# X09-V2_0_0.net
KiCad netlist of a schematic drawn in Altium Designer
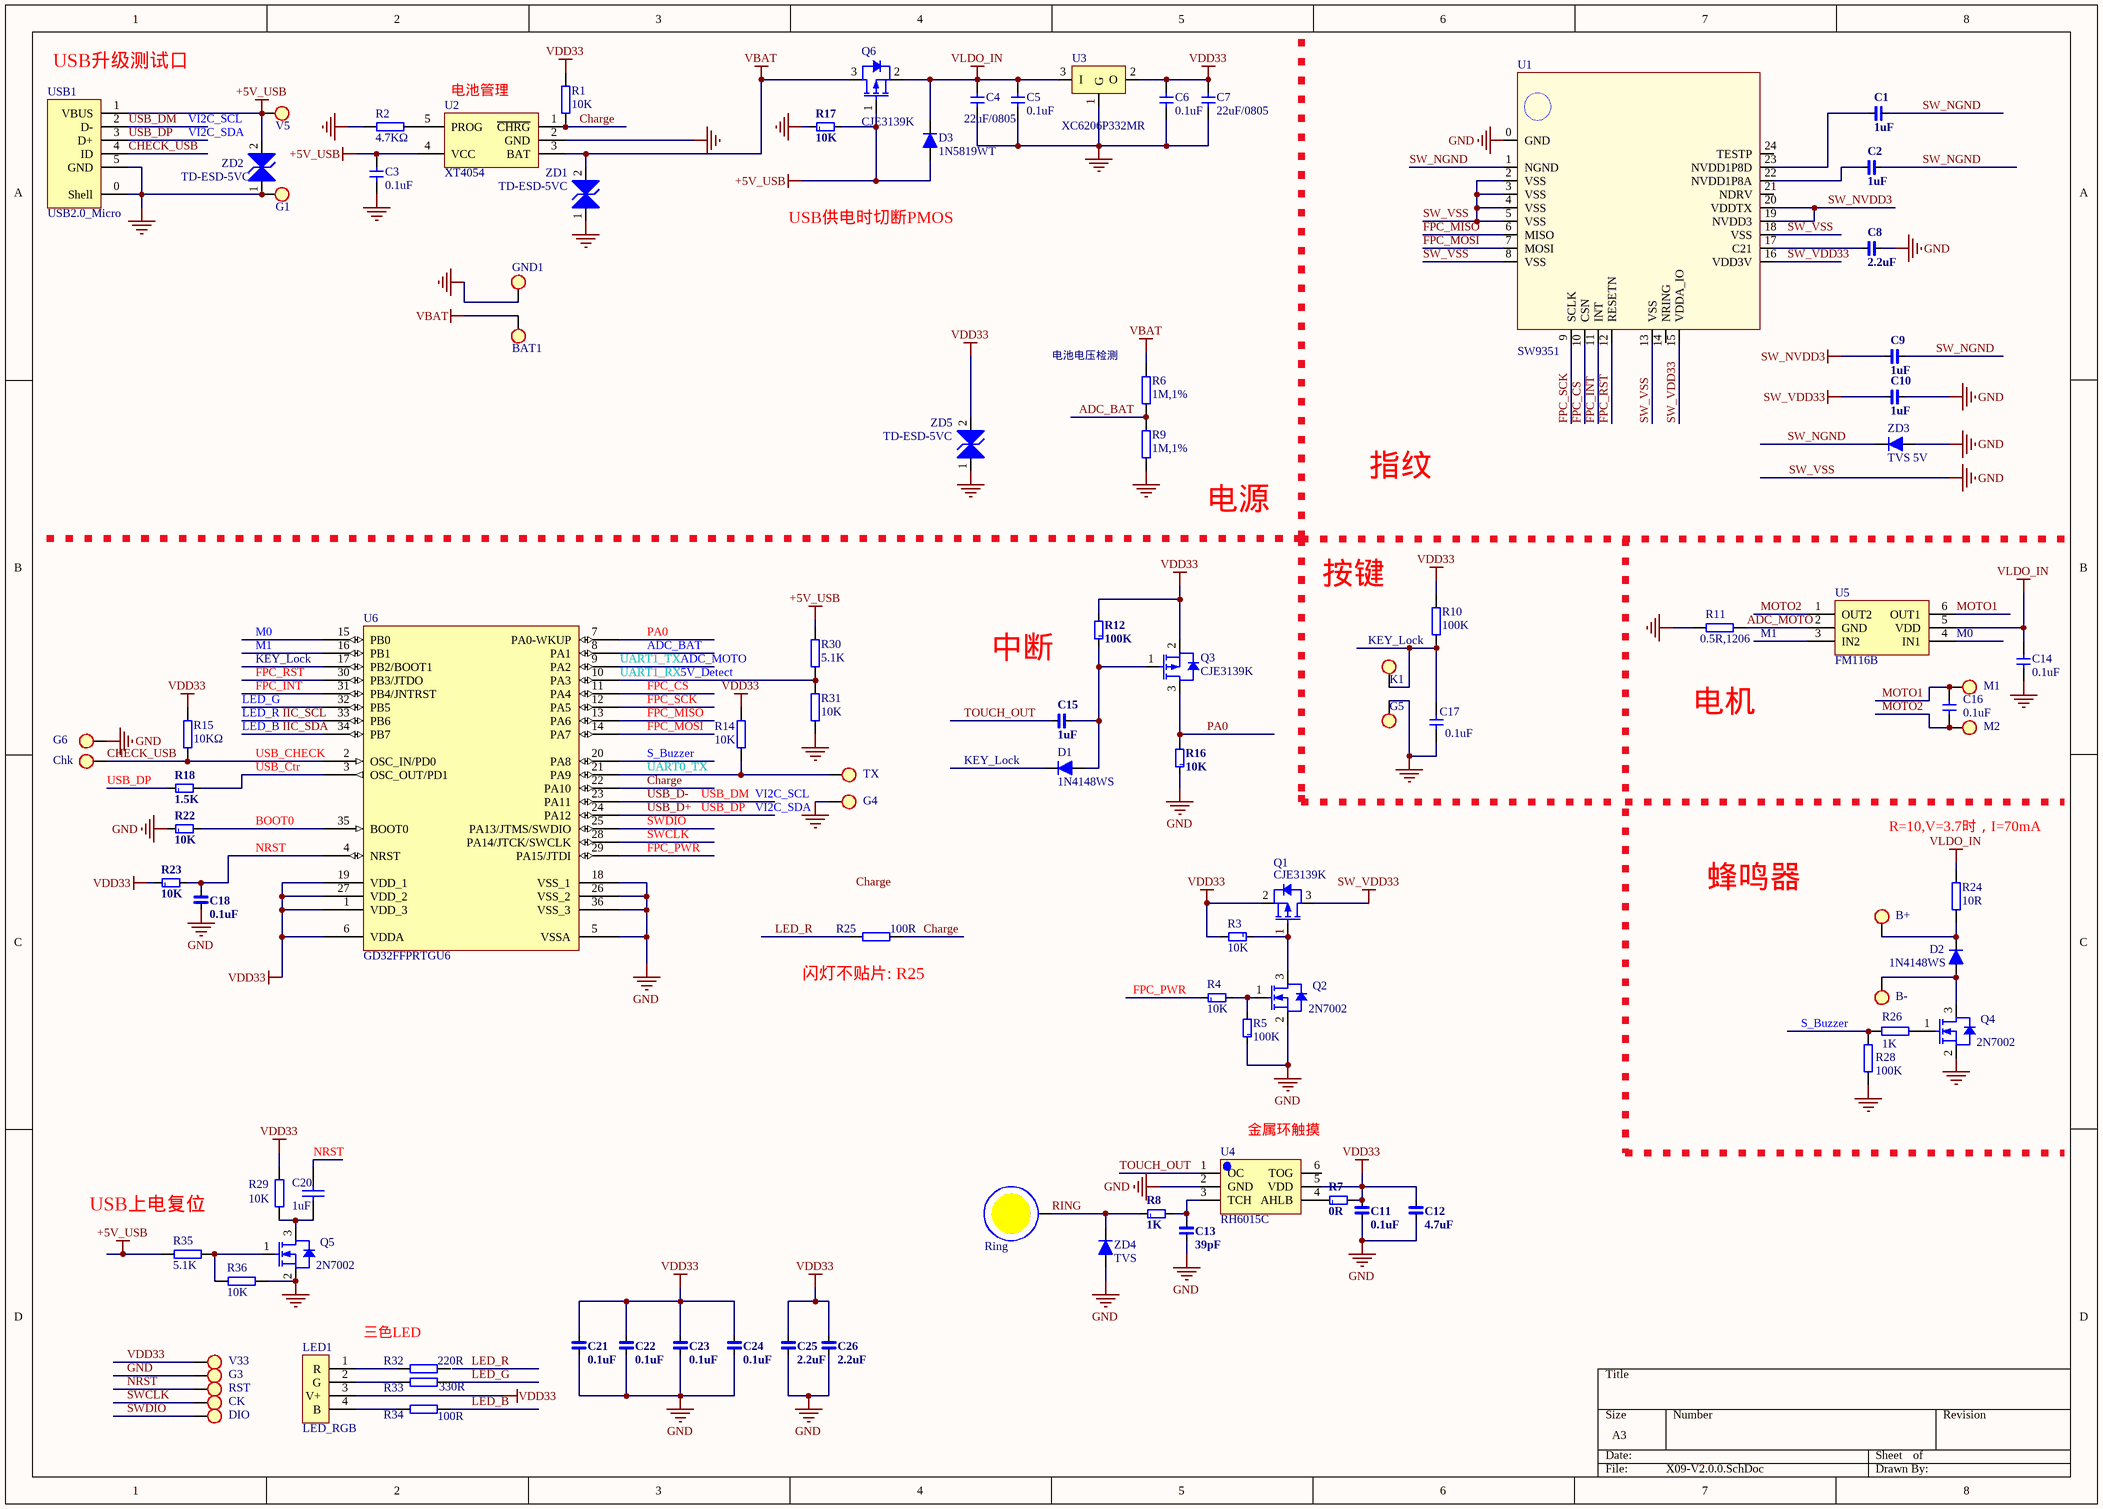
[diagram p0: X09-V2.0.0.SchDoc]

(export (version "E")
  (design (tool "Eeschema 10.0.6"))
  (components
    (comp (ref "B+") (value "TestPoint") (footprint "TEST Point") (libsource (lib "") (part "TestPoint_1")))
    (comp (ref "B-") (value "TestPoint") (footprint "TEST Point") (libsource (lib "") (part "TestPoint_1")))
    (comp (ref "BAT1") (value "TestPoint") (footprint "TEST Point") (libsource (lib "") (part "TestPoint_1")))
    (comp (ref "C1")
      (value "1uF")
      (footprint "0402C")
      (description "Capacitor")
      (libsource (lib "S3C2416") (part "CAP_0402A"))
    )
    (comp (ref "C2")
      (value "1uF")
      (footprint "0402C")
      (description "Capacitor")
      (libsource (lib "S3C2416") (part "CAP_0402A"))
    )
    (comp (ref "C3")
      (value "0.1uF")
      (footprint "0402C")
      (description "Capacitor")
      (libsource (lib "*") (part "CAP"))
    )
    (comp (ref "C4")
      (value "22uF/0805")
      (footprint "0603c")
      (description "Capacitor")
      (libsource (lib "*") (part "CAP"))
    )
    (comp (ref "C5")
      (value "0.1uF")
      (footprint "0402C")
      (description "Capacitor")
      (libsource (lib "*") (part "CAP"))
    )
    (comp (ref "C6")
      (value "0.1uF")
      (footprint "0402C")
      (description "Capacitor")
      (libsource (lib "*") (part "CAP"))
    )
    (comp (ref "C7")
      (value "22uF/0805")
      (footprint "0603c")
      (description "Capacitor")
      (libsource (lib "*") (part "CAP"))
    )
    (comp (ref "C8")
      (value "2.2uF")
      (footprint "0402C")
      (description "Capacitor")
      (libsource (lib "S3C2416") (part "CAP_0402A"))
    )
    (comp (ref "C9")
      (value "1uF")
      (footprint "0402C")
      (description "Capacitor")
      (libsource (lib "S3C2416") (part "CAP_0402A"))
    )
    (comp (ref "C10")
      (value "1uF")
      (footprint "0402C")
      (description "Capacitor")
      (libsource (lib "S3C2416") (part "CAP_0402A"))
    )
    (comp (ref "C11")
      (value "0.1uF")
      (footprint "0402C")
      (description "Capacitor")
      (libsource (lib "S3C2416") (part "CAP_0402A"))
    )
    (comp (ref "C12")
      (value "4.7uF")
      (footprint "0402C")
      (description "Capacitor")
      (libsource (lib "S3C2416") (part "CAP_0402A"))
    )
    (comp (ref "C13")
      (value "39pF")
      (footprint "0402C")
      (description "Capacitor")
      (libsource (lib "S3C2416") (part "CAP_0402A"))
    )
    (comp (ref "C14")
      (value "0.1uF")
      (footprint "0402C")
      (description "Capacitor")
      (libsource (lib "*") (part "CAP"))
    )
    (comp (ref "C15")
      (value "1uF")
      (footprint "0402C")
      (description "Capacitor")
      (libsource (lib "S3C2416") (part "CAP_0402A"))
    )
    (comp (ref "C16")
      (value "0.1uF")
      (footprint "0402C")
      (description "Capacitor")
      (libsource (lib "*") (part "CAP"))
    )
    (comp (ref "C17")
      (value "0.1uF")
      (footprint "0402C")
      (description "Capacitor")
      (libsource (lib "*") (part "CAP"))
    )
    (comp (ref "C18")
      (value "0.1uF")
      (footprint "0402C")
      (description "Capacitor")
      (libsource (lib "S3C2416") (part "CAP_0402A"))
    )
    (comp (ref "C20")
      (value "1uF")
      (footprint "0402C")
      (description "表贴电容")
      (libsource (lib "*") (part "50V/0.1uF"))
    )
    (comp (ref "C21")
      (value "0.1uF")
      (footprint "0402C")
      (description "Capacitor")
      (libsource (lib "S3C2416") (part "CAP_0402A"))
    )
    (comp (ref "C22")
      (value "0.1uF")
      (footprint "0402C")
      (description "Capacitor")
      (libsource (lib "S3C2416") (part "CAP_0402A"))
    )
    (comp (ref "C23")
      (value "0.1uF")
      (footprint "0402C")
      (description "Capacitor")
      (libsource (lib "S3C2416") (part "CAP_0402A"))
    )
    (comp (ref "C24")
      (value "0.1uF")
      (footprint "0402C")
      (description "Capacitor")
      (libsource (lib "S3C2416") (part "CAP_0402A"))
    )
    (comp (ref "C25")
      (value "2.2uF")
      (footprint "0402C")
      (description "Capacitor")
      (libsource (lib "S3C2416") (part "CAP_0402A"))
    )
    (comp (ref "C26")
      (value "2.2uF")
      (footprint "0402C")
      (description "Capacitor")
      (libsource (lib "S3C2416") (part "CAP_0402A"))
    )
    (comp (ref "Chk")
      (value "TestPoint")
      (footprint "TEST Point")
      (libsource (lib "SCH_LIB_WLF") (part "TestPoint"))
    )
    (comp (ref "CK")
      (value "TestPoint")
      (footprint "TEST Point")
      (libsource (lib "SCH_LIB_WLF") (part "TestPoint"))
    )
    (comp (ref "D1") (value "1N4148WS") (footprint "SOD-523") (libsource (lib "PadLock_V3.0") (part "DIODE")))
    (comp (ref "D2") (value "1N4148WS") (footprint "SOD-523") (libsource (lib "PadLock_V3.0") (part "DIODE")))
    (comp (ref "D3") (value "1N5819WT") (footprint "SOD-523") (libsource (lib "PadLock_V3.0") (part "DIODE")))
    (comp (ref "DIO")
      (value "TestPoint")
      (footprint "TEST Point")
      (libsource (lib "SCH_LIB_WLF") (part "TestPoint"))
    )
    (comp (ref "G1")
      (value "TestPoint")
      (footprint "TEST Point")
      (libsource (lib "SCH_LIB_WLF") (part "TestPoint"))
    )
    (comp (ref "G3")
      (value "TestPoint")
      (footprint "TEST Point")
      (libsource (lib "SCH_LIB_WLF") (part "TestPoint"))
    )
    (comp (ref "G4")
      (value "TestPoint")
      (footprint "TEST Point")
      (libsource (lib "SCH_LIB_WLF") (part "TestPoint"))
    )
    (comp (ref "G5") (value "TestPoint") (footprint "TEST Point") (libsource (lib "") (part "TestPoint_1")))
    (comp (ref "G6")
      (value "TestPoint")
      (footprint "TEST Point")
      (libsource (lib "SCH_LIB_WLF") (part "TestPoint"))
    )
    (comp (ref "GND1") (value "TestPoint") (footprint "TEST Point") (libsource (lib "") (part "TestPoint_1")))
    (comp (ref "K1") (value "TestPoint") (footprint "TEST Point") (libsource (lib "") (part "TestPoint_1")))
    (comp (ref "LED1")
      (value "LED_RGB")
      (footprint "LED0603_RGB")
      (libsource (lib "SCH_LIB_WLF") (part "LED_RGB"))
    )
    (comp (ref "M1")
      (value "TestPoint")
      (footprint "TEST Point")
      (libsource (lib "SCH_LIB_WLF") (part "TestPoint"))
    )
    (comp (ref "M2")
      (value "TestPoint")
      (footprint "TEST Point")
      (libsource (lib "SCH_LIB_WLF") (part "TestPoint"))
    )
    (comp (ref "Q1")
      (value "CJE3139K")
      (footprint "SOT-523")
      (description "P-Channel MOSFET")
      (fields (field (name "PUBLISHER") "Altium Limited"))
      (libsource (lib "SCH_LIB_WLF") (part "MOSFET-P"))
    )
    (comp (ref "Q2")
      (value "2N7002")
      (footprint "SOT-523")
      (description "N-Channel MOSFET")
      (fields (field (name "PUBLISHER") "Altium Limited"))
      (libsource (lib "SCH_LIB_WLF") (part "MOSFET-N"))
    )
    (comp (ref "Q3")
      (value "CJE3139K")
      (footprint "SOT-523")
      (description "P-Channel MOSFET")
      (fields (field (name "PUBLISHER") "Altium Limited"))
      (libsource (lib "") (part "MOSFET-P_1"))
    )
    (comp (ref "Q4")
      (value "2N7002")
      (footprint "SOT-523")
      (description "N-Channel MOSFET")
      (fields (field (name "PUBLISHER") "Altium Limited"))
      (libsource (lib "SCH_LIB_WLF") (part "MOSFET-N"))
    )
    (comp (ref "Q5")
      (value "2N7002")
      (footprint "SOT-523")
      (description "N-Channel MOSFET")
      (fields (field (name "PUBLISHER") "Altium Limited"))
      (libsource (lib "SCH_LIB_WLF") (part "MOSFET-N"))
    )
    (comp (ref "Q6")
      (value "CJE3139K")
      (footprint "SOT-523")
      (description "P-Channel MOSFET")
      (fields (field (name "PUBLISHER") "Altium Limited"))
      (libsource (lib "SCH_LIB_WLF") (part "MOSFET-P"))
    )
    (comp (ref "R1")
      (value "10K")
      (footprint "0402R")
      (description "直插/表贴电阻")
      (libsource (lib "*") (part "10KΩ"))
    )
    (comp (ref "R2")
      (value "4.7KΩ")
      (footprint "0402R")
      (description "直插/表贴电阻")
      (libsource (lib "*") (part "10KΩ"))
    )
    (comp (ref "R3")
      (value "10K")
      (footprint "0402R")
      (description "Resistor")
      (libsource (lib "S3C2416") (part "RES_0603A"))
    )
    (comp (ref "R4")
      (value "10K")
      (footprint "0402R")
      (description "Resistor")
      (libsource (lib "S3C2416") (part "RES_0603A"))
    )
    (comp (ref "R5")
      (value "100K")
      (footprint "0402R")
      (description "Resistor")
      (libsource (lib "S3C2416") (part "RES_0603A"))
    )
    (comp (ref "R6")
      (value "1M,1%")
      (footprint "0402R")
      (description "直插/表贴电阻")
      (libsource (lib "*") (part "10KΩ"))
    )
    (comp (ref "R7")
      (value "0R")
      (footprint "0402R")
      (description "Resistor")
      (libsource (lib "S3C2416") (part "RES_0402A"))
    )
    (comp (ref "R8")
      (value "1K")
      (footprint "0402R")
      (description "Resistor")
      (libsource (lib "S3C2416") (part "RES_0402A"))
    )
    (comp (ref "R9")
      (value "1M,1%")
      (footprint "0402R")
      (description "直插/表贴电阻")
      (libsource (lib "*") (part "10KΩ"))
    )
    (comp (ref "R10")
      (value "100K")
      (footprint "0402R")
      (description "直插/表贴电阻")
      (libsource (lib "*") (part "10KΩ"))
    )
    (comp (ref "R11")
      (value "0.5R,1206")
      (footprint "1206")
      (description "直插/表贴电阻")
      (libsource (lib "*") (part "10KΩ"))
    )
    (comp (ref "R12")
      (value "100K")
      (footprint "0402R")
      (description "Resistor")
      (libsource (lib "S3C2416") (part "RES_0402A"))
    )
    (comp (ref "R14")
      (value "10K")
      (footprint "0402R")
      (description "直插/表贴电阻")
      (libsource (lib "*") (part "10KΩ"))
    )
    (comp (ref "R15")
      (value "10KΩ")
      (footprint "0402R")
      (description "直插/表贴电阻")
      (libsource (lib "*") (part "10KΩ"))
    )
    (comp (ref "R16")
      (value "10K")
      (footprint "0402R")
      (description "Resistor")
      (libsource (lib "S3C2416") (part "RES_0402A"))
    )
    (comp (ref "R17")
      (value "10K")
      (footprint "0402R")
      (description "Resistor")
      (libsource (lib "S3C2416") (part "RES_0402A"))
    )
    (comp (ref "R18")
      (value "1.5K")
      (footprint "0402R")
      (description "Resistor")
      (libsource (lib "S3C2416") (part "RES_0402A"))
    )
    (comp (ref "R22")
      (value "10K")
      (footprint "0402R")
      (description "Resistor")
      (libsource (lib "S3C2416") (part "RES_0402A"))
    )
    (comp (ref "R23")
      (value "10K")
      (footprint "0402R")
      (description "Resistor")
      (libsource (lib "S3C2416") (part "RES_0402A"))
    )
    (comp (ref "R24") (value "10R") (footprint "0402R") (libsource (lib "*") (part "RES2")))
    (comp (ref "R25")
      (value "100R")
      (footprint "0402R")
      (description "直插/表贴电阻")
      (libsource (lib "*") (part "10KΩ"))
    )
    (comp (ref "R26")
      (value "1K")
      (footprint "0402R")
      (description "直插/表贴电阻")
      (libsource (lib "*") (part "10KΩ"))
    )
    (comp (ref "R28")
      (value "100K")
      (footprint "0402R")
      (description "直插/表贴电阻")
      (libsource (lib "*") (part "10KΩ"))
    )
    (comp (ref "R29")
      (value "10K")
      (footprint "0402R")
      (description "直插/表贴电阻")
      (libsource (lib "*") (part "10KΩ"))
    )
    (comp (ref "R30")
      (value "5.1K")
      (footprint "0402R")
      (description "直插/表贴电阻")
      (libsource (lib "*") (part "10KΩ"))
    )
    (comp (ref "R31")
      (value "10K")
      (footprint "0402R")
      (description "直插/表贴电阻")
      (libsource (lib "*") (part "10KΩ"))
    )
    (comp (ref "R32")
      (value "220R")
      (footprint "0402R")
      (description "直插/表贴电阻")
      (libsource (lib "*") (part "10KΩ"))
    )
    (comp (ref "R33")
      (value "330R")
      (footprint "0402R")
      (description "直插/表贴电阻")
      (libsource (lib "*") (part "10KΩ"))
    )
    (comp (ref "R34")
      (value "100R")
      (footprint "0402R")
      (description "直插/表贴电阻")
      (libsource (lib "*") (part "10KΩ"))
    )
    (comp (ref "R35")
      (value "5.1K")
      (footprint "0402R")
      (description "直插/表贴电阻")
      (libsource (lib "*") (part "10KΩ"))
    )
    (comp (ref "R36")
      (value "10K")
      (footprint "0402R")
      (description "直插/表贴电阻")
      (libsource (lib "*") (part "10KΩ"))
    )
    (comp (ref "Ring")
      (value "TouchKey")
      (footprint "TouchPad")
      (libsource (lib "SCH_LIB_WLF") (part "TouchKey"))
    )
    (comp (ref "RST")
      (value "TestPoint")
      (footprint "TEST Point")
      (libsource (lib "SCH_LIB_WLF") (part "TestPoint"))
    )
    (comp (ref "TX")
      (value "TestPoint")
      (footprint "TEST Point")
      (libsource (lib "SCH_LIB_WLF") (part "TestPoint"))
    )
    (comp (ref "U1") (value "SW9351") (footprint "SW9551L_1") (libsource (lib "Sheet2") (part "SW9551_120")))
    (comp (ref "U2")
      (value "XT4054")
      (footprint "LC-SOT-23-5")
      (description "电池管理芯片")
      (libsource (lib "SCH_LIB_WLF") (part "4054"))
    )
    (comp (ref "U3")
      (value "XC6206P332MR-G")
      (footprint "SOT-23-standard")
      (description "电源IC")
      (fields (field (name "1ERP_VALUE") "XC6206P332MR"))
      (libsource (lib "SCH") (part "XC6206P182MR-G"))
    )
    (comp (ref "U4")
      (value "RH6015C")
      (footprint "LC-SOT-23-6")
      (description "单通道触摸IC,SOT23-6")
      (libsource (lib "SCH_LIB_WLF") (part "RH6015C"))
    )
    (comp (ref "U5")
      (value "FM116B")
      (footprint "LC-SOT-23-6")
      (description "电机驱动")
      (libsource (lib "SCH_LIB_WLF") (part "FM116B"))
    )
    (comp (ref "U6")
      (value "GD32FFPRTGU6")
      (footprint "GD32GU6-TOP")
      (libsource (lib "*") (part "GD32FFPRTGU6"))
    )
    (comp (ref "USB1")
      (value "USB2.0_Micro")
      (footprint "USB2.0_Micro")
      (libsource (lib "SCH_LIB_WLF") (part "USB2.0_Mini_Micro"))
    )
    (comp (ref "V5")
      (value "TestPoint")
      (footprint "TEST Point")
      (libsource (lib "SCH_LIB_WLF") (part "TestPoint"))
    )
    (comp (ref "V33")
      (value "TestPoint")
      (footprint "TEST Point")
      (libsource (lib "SCH_LIB_WLF") (part "TestPoint"))
    )
    (comp (ref "ZD1")
      (value "TD-ESD-5VC")
      (footprint "SOD-523")
      (libsource (lib "MULTI_TOOL_V 1.6") (part "TVS-DUAL"))
    )
    (comp (ref "ZD2")
      (value "TD-ESD-5VC")
      (footprint "SOD-523")
      (libsource (lib "MULTI_TOOL_V 1.6") (part "TVS-DUAL"))
    )
    (comp (ref "ZD3") (value "TVS 5V") (footprint "SOD-523") (libsource (lib "PadLock_V3.0") (part "DIODE")))
    (comp (ref "ZD4") (value "TVS") (footprint "SOD-523") (libsource (lib "PadLock_V3.0") (part "DIODE")))
    (comp (ref "ZD5")
      (value "TD-ESD-5VC")
      (footprint "SOD-523")
      (libsource (lib "MULTI_TOOL_V 1.6") (part "TVS-DUAL"))
    )
  )
  (nets
    (net (code "1") (name "+5V_USB") (class "Default")
      (node (ref "C3") (pin "1") (pinfunction "1_1") (pintype "passive"))
      (node (ref "D3") (pin "1") (pinfunction "A_1") (pintype "passive"))
      (node (ref "Q6") (pin "1") (pinfunction "G_1") (pintype "passive"))
      (node (ref "R17") (pin "2") (pinfunction "2_2") (pintype "passive"))
      (node (ref "R30") (pin "1") (pinfunction "1_1") (pintype "passive"))
      (node (ref "R35") (pin "2") (pinfunction "2_2") (pintype "passive"))
      (node (ref "U2") (pin "4") (pinfunction "VCC_4") (pintype "passive"))
      (node (ref "USB1") (pin "1") (pinfunction "VBUS_1") (pintype "passive"))
      (node (ref "V5") (pin "1") (pinfunction "Test_1") (pintype "passive"))
      (node (ref "ZD2") (pin "2") (pinfunction "A_2") (pintype "passive"))
    )
    (net (code "2") (name "/5V_Detect") (class "Default")
      (node (ref "R30") (pin "2") (pinfunction "2_2") (pintype "passive"))
      (node (ref "R31") (pin "1") (pinfunction "1_1") (pintype "passive"))
      (node (ref "U6") (pin "10") (pinfunction "PA3_10") (pintype "bidirectional"))
    )
    (net (code "3") (name "/ADC_BAT") (class "Default")
      (node (ref "R6") (pin "2") (pinfunction "2_2") (pintype "passive"))
      (node (ref "R9") (pin "1") (pinfunction "1_1") (pintype "passive"))
      (node (ref "U6") (pin "8") (pinfunction "PA1_8") (pintype "bidirectional"))
    )
    (net (code "4") (name "/ADC_MOTO") (class "Default")
      (node (ref "R11") (pin "2") (pinfunction "2_2") (pintype "passive"))
      (node (ref "U5") (pin "2") (pinfunction "GND_2") (pintype "passive"))
      (node (ref "U6") (pin "9") (pinfunction "PA2_9") (pintype "bidirectional"))
    )
    (net (code "5") (name "/BOOT0") (class "Default")
      (node (ref "R22") (pin "2") (pinfunction "2_2") (pintype "passive"))
      (node (ref "U6") (pin "35") (pinfunction "BOOT0_35") (pintype "input"))
    )
    (net (code "6") (name "/CHECK_USB") (class "Default")
      (node (ref "Chk") (pin "1") (pinfunction "Test_1") (pintype "passive"))
      (node (ref "R15") (pin "1") (pinfunction "1_1") (pintype "passive"))
      (node (ref "U6") (pin "2") (pinfunction "OSC_IN/PD0_2") (pintype "input"))
      (node (ref "USB1") (pin "4") (pinfunction "ID_4") (pintype "passive"))
    )
    (net (code "7") (name "/Charge") (class "Default")
      (node (ref "R1") (pin "2") (pinfunction "2_2") (pintype "passive"))
      (node (ref "R25") (pin "1") (pinfunction "1_1") (pintype "passive"))
      (node (ref "U2") (pin "1") (pinfunction "~{CHRG}_1") (pintype "passive"))
      (node (ref "U6") (pin "22") (pinfunction "PA10_22") (pintype "bidirectional"))
    )
    (net (code "8") (name "/FPC_CS") (class "Default")
      (node (ref "U1") (pin "10") (pinfunction "CSN_10") (pintype "passive"))
      (node (ref "U6") (pin "11") (pinfunction "PA4_11") (pintype "bidirectional"))
    )
    (net (code "9") (name "/FPC_INT") (class "Default")
      (node (ref "U1") (pin "11") (pinfunction "INT_11") (pintype "passive"))
      (node (ref "U6") (pin "31") (pinfunction "PB4/JNTRST_31") (pintype "bidirectional"))
    )
    (net (code "10") (name "/FPC_MISO") (class "Default")
      (node (ref "U1") (pin "6") (pinfunction "MISO_6") (pintype "passive"))
      (node (ref "U6") (pin "13") (pinfunction "PA6_13") (pintype "bidirectional"))
    )
    (net (code "11") (name "/FPC_MOSI") (class "Default")
      (node (ref "U1") (pin "7") (pinfunction "MOSI_7") (pintype "passive"))
      (node (ref "U6") (pin "14") (pinfunction "PA7_14") (pintype "bidirectional"))
    )
    (net (code "12") (name "/FPC_PWR") (class "Default")
      (node (ref "R4") (pin "1") (pinfunction "1_1") (pintype "passive"))
      (node (ref "U6") (pin "29") (pinfunction "PA15/JTDI_29") (pintype "bidirectional"))
    )
    (net (code "13") (name "/FPC_RST") (class "Default")
      (node (ref "U1") (pin "12") (pinfunction "RESETN_12") (pintype "passive"))
      (node (ref "U6") (pin "30") (pinfunction "PB3/JTDO_30") (pintype "bidirectional"))
    )
    (net (code "14") (name "/FPC_SCK") (class "Default")
      (node (ref "U1") (pin "9") (pinfunction "SCLK_9") (pintype "passive"))
      (node (ref "U6") (pin "12") (pinfunction "PA5_12") (pintype "bidirectional"))
    )
    (net (code "15") (name "/IIC_SCL") (class "Default")
      (node (ref "R25") (pin "2") (pinfunction "2_2") (pintype "passive"))
      (node (ref "U6") (pin "33") (pinfunction "PB6_33") (pintype "bidirectional"))
    )
    (net (code "16") (name "/IIC_SDA") (class "Default")
      (node (ref "R34") (pin "1") (pinfunction "1_1") (pintype "passive"))
      (node (ref "U6") (pin "34") (pinfunction "PB7_34") (pintype "bidirectional"))
    )
    (net (code "17") (name "/KEY_Lock") (class "Default")
      (node (ref "C17") (pin "1") (pinfunction "1_1") (pintype "passive"))
      (node (ref "D1") (pin "2") (pinfunction "K_2") (pintype "passive"))
      (node (ref "K1") (pin "1") (pinfunction "Test_1") (pintype "passive"))
      (node (ref "R10") (pin "2") (pinfunction "2_2") (pintype "passive"))
      (node (ref "U6") (pin "17") (pinfunction "PB2/BOOT1_17") (pintype "bidirectional"))
    )
    (net (code "18") (name "/LED_G") (class "Default")
      (node (ref "R33") (pin "1") (pinfunction "1_1") (pintype "passive"))
      (node (ref "U6") (pin "32") (pinfunction "PB5_32") (pintype "bidirectional"))
    )
    (net (code "19") (name "/M0") (class "Default")
      (node (ref "U5") (pin "4") (pinfunction "IN1_4") (pintype "passive"))
      (node (ref "U6") (pin "15") (pinfunction "PB0_15") (pintype "bidirectional"))
    )
    (net (code "20") (name "/M1") (class "Default")
      (node (ref "U5") (pin "3") (pinfunction "IN2_3") (pintype "passive"))
      (node (ref "U6") (pin "16") (pinfunction "PB1_16") (pintype "bidirectional"))
    )
    (net (code "21") (name "/MOTO1") (class "Default")
      (node (ref "C16") (pin "2") (pinfunction "2_2") (pintype "passive"))
      (node (ref "M1") (pin "1") (pinfunction "Test_1") (pintype "passive"))
      (node (ref "U5") (pin "6") (pinfunction "OUT1_6") (pintype "passive"))
    )
    (net (code "22") (name "/MOTO2") (class "Default")
      (node (ref "C16") (pin "1") (pinfunction "1_1") (pintype "passive"))
      (node (ref "M2") (pin "1") (pinfunction "Test_1") (pintype "passive"))
      (node (ref "U5") (pin "1") (pinfunction "OUT2_1") (pintype "passive"))
    )
    (net (code "23") (name "/NRST") (class "Default")
      (node (ref "C18") (pin "2") (pinfunction "2_2") (pintype "passive"))
      (node (ref "C20") (pin "1") (pinfunction "1_1") (pintype "passive"))
      (node (ref "R23") (pin "2") (pinfunction "2_2") (pintype "passive"))
      (node (ref "RST") (pin "1") (pinfunction "Test_1") (pintype "passive"))
      (node (ref "U6") (pin "4") (pinfunction "NRST_4") (pintype "bidirectional"))
    )
    (net (code "24") (name "/PA0") (class "Default")
      (node (ref "Q3") (pin "3") (pinfunction "D_3") (pintype "passive"))
      (node (ref "R16") (pin "2") (pinfunction "2_2") (pintype "passive"))
      (node (ref "U6") (pin "7") (pinfunction "PA0-WKUP_7") (pintype "bidirectional"))
    )
    (net (code "25") (name "/RING") (class "Default")
      (node (ref "R8") (pin "1") (pinfunction "1_1") (pintype "passive"))
      (node (ref "Ring") (pin "1") (pinfunction "Key_1") (pintype "passive"))
      (node (ref "ZD4") (pin "2") (pinfunction "K_2") (pintype "passive"))
    )
    (net (code "26") (name "/SWCLK") (class "Default")
      (node (ref "CK") (pin "1") (pinfunction "Test_1") (pintype "passive"))
      (node (ref "U6") (pin "28") (pinfunction "PA14/JTCK/SWCLK_28") (pintype "bidirectional"))
    )
    (net (code "27") (name "/SWDIO") (class "Default")
      (node (ref "DIO") (pin "1") (pinfunction "Test_1") (pintype "passive"))
      (node (ref "U6") (pin "25") (pinfunction "PA13/JTMS/SWDIO_25") (pintype "bidirectional"))
    )
    (net (code "28") (name "/SW_NGND") (class "Default")
      (node (ref "C1") (pin "1") (pinfunction "1_1") (pintype "passive"))
      (node (ref "C2") (pin "1") (pinfunction "1_1") (pintype "passive"))
      (node (ref "C9") (pin "1") (pinfunction "1_1") (pintype "passive"))
      (node (ref "U1") (pin "1") (pinfunction "NGND_1") (pintype "passive"))
      (node (ref "ZD3") (pin "2") (pinfunction "K_2") (pintype "passive"))
    )
    (net (code "29") (name "/S_Buzzer") (class "Default")
      (node (ref "R26") (pin "2") (pinfunction "2_2") (pintype "passive"))
      (node (ref "R28") (pin "1") (pinfunction "1_1") (pintype "passive"))
      (node (ref "U6") (pin "20") (pinfunction "PA8_20") (pintype "bidirectional"))
    )
    (net (code "30") (name "/TOUCH_OUT") (class "Default")
      (node (ref "C15") (pin "2") (pinfunction "2_2") (pintype "passive"))
      (node (ref "U4") (pin "1") (pinfunction "OC_1") (pintype "passive"))
    )
    (net (code "31") (name "/UART0_TX") (class "Default")
      (node (ref "R14") (pin "2") (pinfunction "2_2") (pintype "passive"))
      (node (ref "TX") (pin "1") (pinfunction "Test_1") (pintype "passive"))
      (node (ref "U6") (pin "21") (pinfunction "PA9_21") (pintype "bidirectional"))
    )
    (net (code "32") (name "/USB_Ctr") (class "Default")
      (node (ref "R18") (pin "2") (pinfunction "2_2") (pintype "passive"))
      (node (ref "U6") (pin "3") (pinfunction "OSC_OUT/PD1_3") (pintype "output"))
    )
    (net (code "33") (name "/USB_D+") (class "Default")
      (node (ref "R18") (pin "1") (pinfunction "1_1") (pintype "passive"))
      (node (ref "U6") (pin "24") (pinfunction "PA12_24") (pintype "bidirectional"))
      (node (ref "USB1") (pin "3") (pinfunction "D+_3") (pintype "passive"))
    )
    (net (code "34") (name "/USB_D-") (class "Default")
      (node (ref "U6") (pin "23") (pinfunction "PA11_23") (pintype "bidirectional"))
      (node (ref "USB1") (pin "2") (pinfunction "D-_2") (pintype "passive"))
    )
    (net (code "35") (name "GND") (class "Default")
      (node (ref "C10") (pin "1") (pinfunction "1_1") (pintype "passive"))
      (node (ref "C11") (pin "1") (pinfunction "1_1") (pintype "passive"))
      (node (ref "C12") (pin "1") (pinfunction "1_1") (pintype "passive"))
      (node (ref "C13") (pin "1") (pinfunction "1_1") (pintype "passive"))
      (node (ref "C14") (pin "1") (pinfunction "1_1") (pintype "passive"))
      (node (ref "C17") (pin "2") (pinfunction "2_2") (pintype "passive"))
      (node (ref "C18") (pin "1") (pinfunction "1_1") (pintype "passive"))
      (node (ref "C21") (pin "1") (pinfunction "1_1") (pintype "passive"))
      (node (ref "C22") (pin "1") (pinfunction "1_1") (pintype "passive"))
      (node (ref "C23") (pin "1") (pinfunction "1_1") (pintype "passive"))
      (node (ref "C24") (pin "1") (pinfunction "1_1") (pintype "passive"))
      (node (ref "C25") (pin "1") (pinfunction "1_1") (pintype "passive"))
      (node (ref "C26") (pin "1") (pinfunction "1_1") (pintype "passive"))
      (node (ref "C3") (pin "2") (pinfunction "2_2") (pintype "passive"))
      (node (ref "C4") (pin "2") (pinfunction "2_2") (pintype "passive"))
      (node (ref "C5") (pin "2") (pinfunction "2_2") (pintype "passive"))
      (node (ref "C6") (pin "2") (pinfunction "2_2") (pintype "passive"))
      (node (ref "C7") (pin "2") (pinfunction "2_2") (pintype "passive"))
      (node (ref "C8") (pin "1") (pinfunction "1_1") (pintype "passive"))
      (node (ref "G1") (pin "1") (pinfunction "Test_1") (pintype "passive"))
      (node (ref "G3") (pin "1") (pinfunction "Test_1") (pintype "passive"))
      (node (ref "G4") (pin "1") (pinfunction "Test_1") (pintype "passive"))
      (node (ref "G5") (pin "1") (pinfunction "Test_1") (pintype "passive"))
      (node (ref "G6") (pin "1") (pinfunction "Test_1") (pintype "passive"))
      (node (ref "GND1") (pin "1") (pinfunction "Test_1") (pintype "passive"))
      (node (ref "Q2") (pin "2") (pinfunction "S_2") (pintype "passive"))
      (node (ref "Q4") (pin "2") (pinfunction "S_2") (pintype "passive"))
      (node (ref "Q5") (pin "2") (pinfunction "S_2") (pintype "passive"))
      (node (ref "R11") (pin "1") (pinfunction "1_1") (pintype "passive"))
      (node (ref "R16") (pin "1") (pinfunction "1_1") (pintype "passive"))
      (node (ref "R17") (pin "1") (pinfunction "1_1") (pintype "passive"))
      (node (ref "R2") (pin "1") (pinfunction "1_1") (pintype "passive"))
      (node (ref "R22") (pin "1") (pinfunction "1_1") (pintype "passive"))
      (node (ref "R28") (pin "2") (pinfunction "2_2") (pintype "passive"))
      (node (ref "R31") (pin "2") (pinfunction "2_2") (pintype "passive"))
      (node (ref "R36") (pin "2") (pinfunction "2_2") (pintype "passive"))
      (node (ref "R5") (pin "1") (pinfunction "1_1") (pintype "passive"))
      (node (ref "R9") (pin "2") (pinfunction "2_2") (pintype "passive"))
      (node (ref "U1") (pin "0") (pinfunction "GND_0") (pintype "passive"))
      (node (ref "U1") (pin "13") (pinfunction "VSS_13") (pintype "passive"))
      (node (ref "U1") (pin "18") (pinfunction "VSS_18") (pintype "passive"))
      (node (ref "U1") (pin "2") (pinfunction "VSS_2") (pintype "passive"))
      (node (ref "U1") (pin "3") (pinfunction "VSS_3") (pintype "passive"))
      (node (ref "U1") (pin "4") (pinfunction "VSS_4") (pintype "passive"))
      (node (ref "U1") (pin "5") (pinfunction "VSS_5") (pintype "passive"))
      (node (ref "U1") (pin "8") (pinfunction "VSS_8") (pintype "passive"))
      (node (ref "U2") (pin "2") (pinfunction "GND_2") (pintype "passive"))
      (node (ref "U3") (pin "1") (pinfunction "G_1") (pintype "passive"))
      (node (ref "U4") (pin "2") (pinfunction "GND_2") (pintype "passive"))
      (node (ref "U6") (pin "18") (pinfunction "VSS_1_18") (pintype "power_in"))
      (node (ref "U6") (pin "26") (pinfunction "VSS_2_26") (pintype "power_in"))
      (node (ref "U6") (pin "36") (pinfunction "VSS_3_36") (pintype "power_in"))
      (node (ref "U6") (pin "5") (pinfunction "VSSA_5") (pintype "power_in"))
      (node (ref "USB1") (pin "0") (pinfunction "Shell_0") (pintype "passive"))
      (node (ref "USB1") (pin "5") (pinfunction "GND_5") (pintype "passive"))
      (node (ref "ZD1") (pin "1") (pinfunction "K_1") (pintype "passive"))
      (node (ref "ZD2") (pin "1") (pinfunction "K_1") (pintype "passive"))
      (node (ref "ZD3") (pin "1") (pinfunction "A_1") (pintype "passive"))
      (node (ref "ZD4") (pin "1") (pinfunction "A_1") (pintype "passive"))
      (node (ref "ZD5") (pin "1") (pinfunction "K_1") (pintype "passive"))
    )
    (net (code "36") (name "Net-(B+-Test)") (class "Default")
      (node (ref "B+") (pin "1") (pinfunction "Test_1") (pintype "passive"))
      (node (ref "D2") (pin "2") (pinfunction "K_2") (pintype "passive"))
      (node (ref "R24") (pin "1") (pinfunction "1_1") (pintype "passive"))
    )
    (net (code "37") (name "Net-(B--Test)") (class "Default")
      (node (ref "B-") (pin "1") (pinfunction "Test_1") (pintype "passive"))
      (node (ref "D2") (pin "1") (pinfunction "A_1") (pintype "passive"))
      (node (ref "Q4") (pin "3") (pinfunction "D_3") (pintype "passive"))
    )
    (net (code "38") (name "Net-(D1-A)") (class "Default")
      (node (ref "C15") (pin "1") (pinfunction "1_1") (pintype "passive"))
      (node (ref "D1") (pin "1") (pinfunction "A_1") (pintype "passive"))
      (node (ref "Q3") (pin "1") (pinfunction "G_1") (pintype "passive"))
      (node (ref "R12") (pin "1") (pinfunction "1_1") (pintype "passive"))
    )
    (net (code "39") (name "Net-(LED1-B)") (class "Default")
      (node (ref "LED1") (pin "4") (pinfunction "B_4") (pintype "passive"))
      (node (ref "R34") (pin "2") (pinfunction "2_2") (pintype "passive"))
    )
    (net (code "40") (name "Net-(LED1-G)") (class "Default")
      (node (ref "LED1") (pin "2") (pinfunction "G_2") (pintype "passive"))
      (node (ref "R33") (pin "2") (pinfunction "2_2") (pintype "passive"))
    )
    (net (code "41") (name "Net-(LED1-R)") (class "Default")
      (node (ref "LED1") (pin "1") (pinfunction "R_1") (pintype "passive"))
      (node (ref "R32") (pin "2") (pinfunction "2_2") (pintype "passive"))
    )
    (net (code "42") (name "Net-(Q1-G)") (class "Default")
      (node (ref "Q1") (pin "1") (pinfunction "G_1") (pintype "passive"))
      (node (ref "Q2") (pin "3") (pinfunction "D_3") (pintype "passive"))
      (node (ref "R3") (pin "1") (pinfunction "1_1") (pintype "passive"))
    )
    (net (code "43") (name "Net-(Q2-G)") (class "Default")
      (node (ref "Q2") (pin "1") (pinfunction "G_1") (pintype "passive"))
      (node (ref "R4") (pin "2") (pinfunction "2_2") (pintype "passive"))
      (node (ref "R5") (pin "2") (pinfunction "2_2") (pintype "passive"))
    )
    (net (code "44") (name "Net-(Q4-G)") (class "Default")
      (node (ref "Q4") (pin "1") (pinfunction "G_1") (pintype "passive"))
      (node (ref "R26") (pin "1") (pinfunction "1_1") (pintype "passive"))
    )
    (net (code "45") (name "Net-(Q5-D)") (class "Default")
      (node (ref "C20") (pin "2") (pinfunction "2_2") (pintype "passive"))
      (node (ref "Q5") (pin "3") (pinfunction "D_3") (pintype "passive"))
      (node (ref "R29") (pin "2") (pinfunction "2_2") (pintype "passive"))
    )
    (net (code "46") (name "Net-(Q5-G)") (class "Default")
      (node (ref "Q5") (pin "1") (pinfunction "G_1") (pintype "passive"))
      (node (ref "R35") (pin "1") (pinfunction "1_1") (pintype "passive"))
      (node (ref "R36") (pin "1") (pinfunction "1_1") (pintype "passive"))
    )
    (net (code "47") (name "Net-(U1-C21)") (class "Default")
      (node (ref "C8") (pin "2") (pinfunction "2_2") (pintype "passive"))
      (node (ref "U1") (pin "17") (pinfunction "C21_17") (pintype "passive"))
    )
    (net (code "48") (name "Net-(U1-NVDD1P8A)") (class "Default")
      (node (ref "C2") (pin "2") (pinfunction "2_2") (pintype "passive"))
      (node (ref "U1") (pin "22") (pinfunction "NVDD1P8A_22") (pintype "passive"))
    )
    (net (code "49") (name "Net-(U1-NVDD1P8D)") (class "Default")
      (node (ref "C1") (pin "2") (pinfunction "2_2") (pintype "passive"))
      (node (ref "U1") (pin "23") (pinfunction "NVDD1P8D_23") (pintype "passive"))
    )
    (net (code "50") (name "Net-(U2-PROG)") (class "Default")
      (node (ref "R2") (pin "2") (pinfunction "2_2") (pintype "passive"))
      (node (ref "U2") (pin "5") (pinfunction "PROG_5") (pintype "passive"))
    )
    (net (code "51") (name "Net-(U4-AHLB)") (class "Default")
      (node (ref "R7") (pin "1") (pinfunction "1_1") (pintype "passive"))
      (node (ref "U4") (pin "4") (pinfunction "AHLB_4") (pintype "passive"))
    )
    (net (code "52") (name "Net-(U4-TCH)") (class "Default")
      (node (ref "C13") (pin "2") (pinfunction "2_2") (pintype "passive"))
      (node (ref "R8") (pin "2") (pinfunction "2_2") (pintype "passive"))
      (node (ref "U4") (pin "3") (pinfunction "TCH_3") (pintype "passive"))
    )
    (net (code "53") (name "SW_NVDD3") (class "Default")
      (node (ref "C9") (pin "2") (pinfunction "2_2") (pintype "passive"))
      (node (ref "U1") (pin "19") (pinfunction "NVDD3_19") (pintype "passive"))
      (node (ref "U1") (pin "20") (pinfunction "VDDTX_20") (pintype "passive"))
    )
    (net (code "54") (name "SW_VDD33") (class "Default")
      (node (ref "C10") (pin "2") (pinfunction "2_2") (pintype "passive"))
      (node (ref "Q1") (pin "3") (pinfunction "D_3") (pintype "passive"))
      (node (ref "U1") (pin "15") (pinfunction "VDDA_IO_15") (pintype "passive"))
      (node (ref "U1") (pin "16") (pinfunction "VDD3V_16") (pintype "passive"))
    )
    (net (code "55") (name "VBAT") (class "Default")
      (node (ref "BAT1") (pin "1") (pinfunction "Test_1") (pintype "passive"))
      (node (ref "Q6") (pin "3") (pinfunction "D_3") (pintype "passive"))
      (node (ref "R6") (pin "1") (pinfunction "1_1") (pintype "passive"))
      (node (ref "U2") (pin "3") (pinfunction "BAT_3") (pintype "passive"))
      (node (ref "ZD1") (pin "2") (pinfunction "A_2") (pintype "passive"))
    )
    (net (code "56") (name "VDD33") (class "Default")
      (node (ref "C11") (pin "2") (pinfunction "2_2") (pintype "passive"))
      (node (ref "C12") (pin "2") (pinfunction "2_2") (pintype "passive"))
      (node (ref "C21") (pin "2") (pinfunction "2_2") (pintype "passive"))
      (node (ref "C22") (pin "2") (pinfunction "2_2") (pintype "passive"))
      (node (ref "C23") (pin "2") (pinfunction "2_2") (pintype "passive"))
      (node (ref "C24") (pin "2") (pinfunction "2_2") (pintype "passive"))
      (node (ref "C25") (pin "2") (pinfunction "2_2") (pintype "passive"))
      (node (ref "C26") (pin "2") (pinfunction "2_2") (pintype "passive"))
      (node (ref "C6") (pin "1") (pinfunction "1_1") (pintype "passive"))
      (node (ref "C7") (pin "1") (pinfunction "1_1") (pintype "passive"))
      (node (ref "LED1") (pin "3") (pinfunction "V+_3") (pintype "passive"))
      (node (ref "Q1") (pin "2") (pinfunction "S_2") (pintype "passive"))
      (node (ref "Q3") (pin "2") (pinfunction "S_2") (pintype "passive"))
      (node (ref "R1") (pin "1") (pinfunction "1_1") (pintype "passive"))
      (node (ref "R10") (pin "1") (pinfunction "1_1") (pintype "passive"))
      (node (ref "R12") (pin "2") (pinfunction "2_2") (pintype "passive"))
      (node (ref "R14") (pin "1") (pinfunction "1_1") (pintype "passive"))
      (node (ref "R15") (pin "2") (pinfunction "2_2") (pintype "passive"))
      (node (ref "R23") (pin "1") (pinfunction "1_1") (pintype "passive"))
      (node (ref "R29") (pin "1") (pinfunction "1_1") (pintype "passive"))
      (node (ref "R3") (pin "2") (pinfunction "2_2") (pintype "passive"))
      (node (ref "R7") (pin "2") (pinfunction "2_2") (pintype "passive"))
      (node (ref "U3") (pin "2") (pinfunction "O_2") (pintype "passive"))
      (node (ref "U4") (pin "5") (pinfunction "VDD_5") (pintype "passive"))
      (node (ref "U6") (pin "1") (pinfunction "VDD_3_1") (pintype "power_in"))
      (node (ref "U6") (pin "19") (pinfunction "VDD_1_19") (pintype "power_in"))
      (node (ref "U6") (pin "27") (pinfunction "VDD_2_27") (pintype "power_in"))
      (node (ref "U6") (pin "6") (pinfunction "VDDA_6") (pintype "power_in"))
      (node (ref "V33") (pin "1") (pinfunction "Test_1") (pintype "passive"))
      (node (ref "ZD5") (pin "2") (pinfunction "A_2") (pintype "passive"))
    )
    (net (code "57") (name "VLDO_IN") (class "Default")
      (node (ref "C14") (pin "2") (pinfunction "2_2") (pintype "passive"))
      (node (ref "C4") (pin "1") (pinfunction "1_1") (pintype "passive"))
      (node (ref "C5") (pin "1") (pinfunction "1_1") (pintype "passive"))
      (node (ref "D3") (pin "2") (pinfunction "K_2") (pintype "passive"))
      (node (ref "Q6") (pin "2") (pinfunction "S_2") (pintype "passive"))
      (node (ref "R24") (pin "2") (pinfunction "2_2") (pintype "passive"))
      (node (ref "U3") (pin "3") (pinfunction "I_3") (pintype "passive"))
      (node (ref "U5") (pin "5") (pinfunction "VDD_5") (pintype "passive"))
    )
    (net (code "58") (name "unconnected-(R32-Pad1)") (class "Default")
      (node (ref "R32") (pin "1") (pinfunction "1_1") (pintype "passive"))
    )
    (net (code "59") (name "unconnected-(U1-NDRV-Pad21)") (class "Default")
      (node (ref "U1") (pin "21") (pinfunction "NDRV_21") (pintype "passive"))
    )
    (net (code "60") (name "unconnected-(U1-NRING-Pad14)") (class "Default")
      (node (ref "U1") (pin "14") (pinfunction "NRING_14") (pintype "passive"))
    )
    (net (code "61") (name "unconnected-(U1-TESTP-Pad24)") (class "Default")
      (node (ref "U1") (pin "24") (pinfunction "TESTP_24") (pintype "passive"))
    )
    (net (code "62") (name "unconnected-(U4-TOG-Pad6)") (class "Default")
      (node (ref "U4") (pin "6") (pinfunction "TOG_6") (pintype "passive"))
    )
  )
)
